# USB_power.net
KiCad netlist of a schematic drawn in Altium Designer
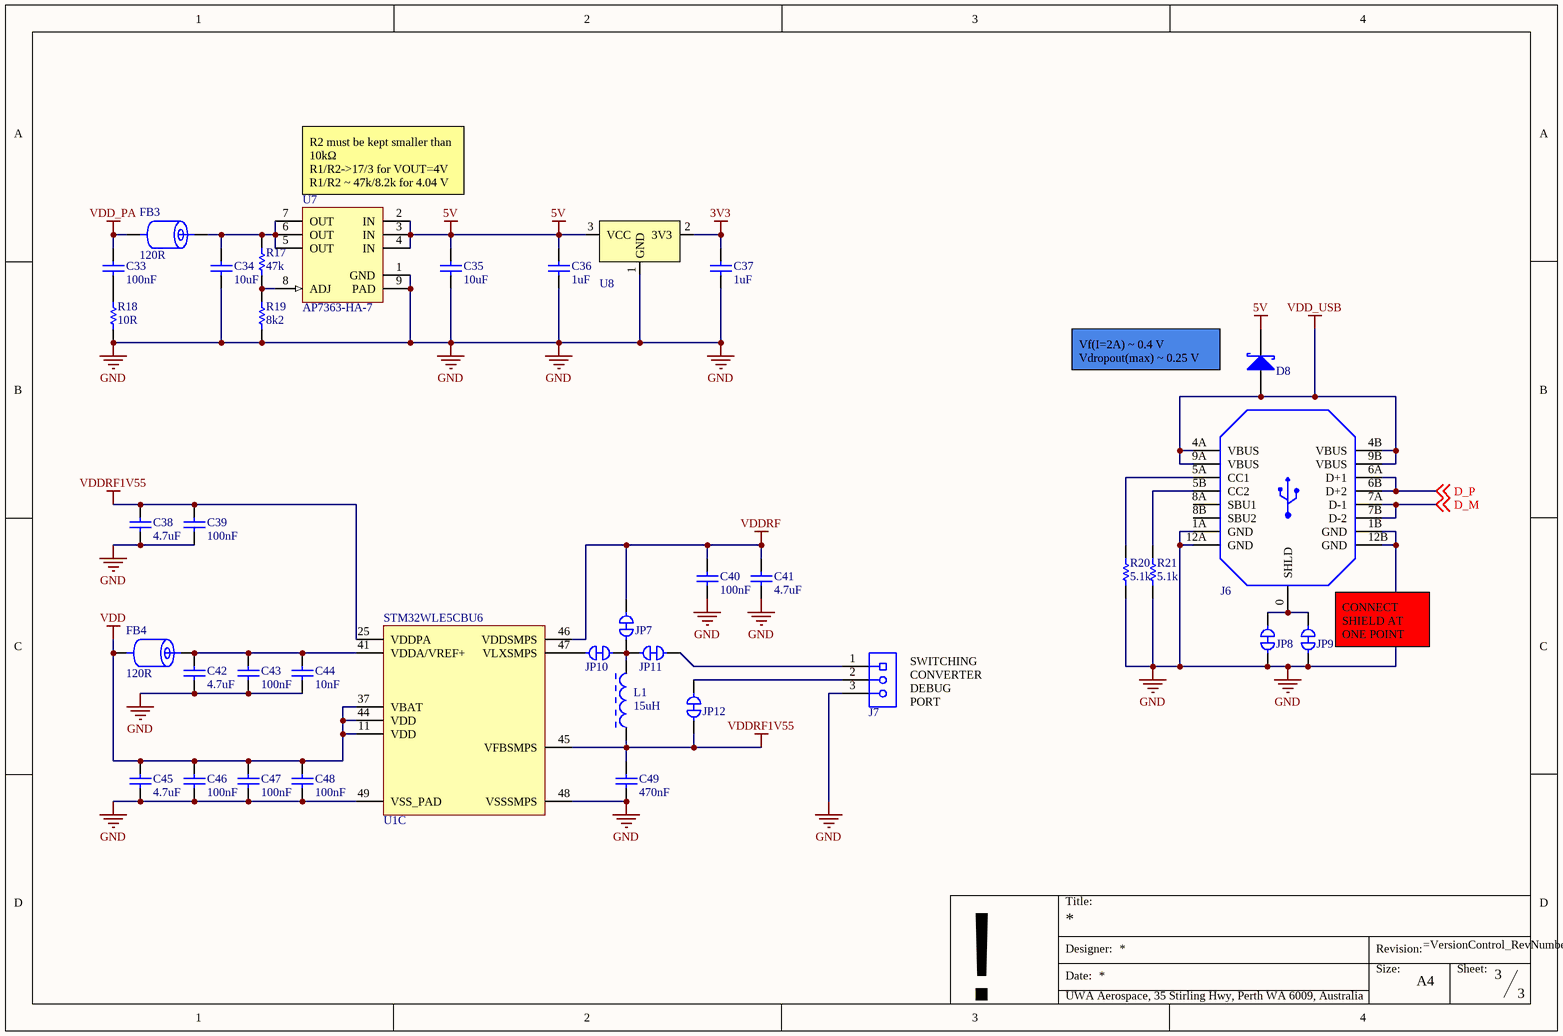
[diagram p0: USB & power.SchDoc]

(export (version "E")
  (design (tool "Eeschema 10.0.6"))
  (components
    (comp (ref "C33")
      (value "100nF")
      (footprint "CAPC1608X10N")
      (description "Cap Ceramic 0.1uF 50V X7R 20% SMD 0603 125C T/R")
      (fields (field (name "TOLERANCE") "20%") (field (name "Comment") "C0603C104M5RACTU"))
      (libsource (lib "UWA Aerospace") (part "C0603C104M5RACTU"))
    )
    (comp (ref "C34")
      (value "10uF")
      (footprint "CAPC2012X14N")
      (description "CAP CER 10UF 10V X5R 0805")
      (fields (field (name "VOLTAGE") "10V") (field (name "TOLERANCE") "10%"))
      (libsource (lib "UWA Aerospace") (part "C0603C104M5RACTU"))
    )
    (comp (ref "C35")
      (value "10uF")
      (footprint "CAPC2012X14N")
      (description "CAP CER 10UF 10V X5R 0805")
      (fields (field (name "VOLTAGE") "10V") (field (name "TOLERANCE") "10%"))
      (libsource (lib "UWA Aerospace") (part "C0603C104M5RACTU"))
    )
    (comp (ref "C36")
      (value "1uF")
      (footprint "CAPC1608X10N")
      (fields
        (field (name "VOLTAGE") "16V")
        (field (name "TOLERANCE") "10%")
        (field (name "Comment") "C0603C105K4RACTU")
      )
      (libsource (lib "UWA Aerospace") (part "C0603C104M5RACTU"))
    )
    (comp (ref "C37")
      (value "1uF")
      (footprint "CAPC1608X10N")
      (fields
        (field (name "VOLTAGE") "16V")
        (field (name "TOLERANCE") "10%")
        (field (name "Comment") "C0603C105K4RACTU")
      )
      (libsource (lib "UWA Aerospace") (part "C0603C104M5RACTU"))
    )
    (comp (ref "C38")
      (value "4.7uF")
      (footprint "CAPC1608X10N")
      (fields
        (field (name "TOLERANCE") "10%")
        (field (name "VOLTAGE") "6.3V")
        (field (name "Comment") "C0603C475K9PACTU")
      )
      (libsource (lib "UWA Aerospace") (part "C0603C104M5RACTU"))
    )
    (comp (ref "C39")
      (value "100nF")
      (footprint "CAPC1608X10N")
      (description "Cap Ceramic 0.1uF 50V X7R 20% SMD 0603 125C T/R")
      (fields (field (name "TOLERANCE") "20%") (field (name "Comment") "C0603C104M5RACTU"))
      (libsource (lib "UWA Aerospace") (part "C0603C104M5RACTU"))
    )
    (comp (ref "C40")
      (value "100nF")
      (footprint "CAPC1608X10N")
      (description "Cap Ceramic 0.1uF 50V X7R 20% SMD 0603 125C T/R")
      (fields (field (name "TOLERANCE") "20%") (field (name "Comment") "C0603C104M5RACTU"))
      (libsource (lib "UWA Aerospace") (part "C0603C104M5RACTU"))
    )
    (comp (ref "C41")
      (value "4.7uF")
      (footprint "CAPC1608X10N")
      (fields
        (field (name "TOLERANCE") "10%")
        (field (name "VOLTAGE") "6.3V")
        (field (name "Comment") "C0603C475K9PACTU")
      )
      (libsource (lib "UWA Aerospace") (part "C0603C104M5RACTU"))
    )
    (comp (ref "C42")
      (value "4.7uF")
      (footprint "CAPC1608X10N")
      (fields
        (field (name "TOLERANCE") "10%")
        (field (name "VOLTAGE") "6.3V")
        (field (name "Comment") "C0603C475K9PACTU")
      )
      (libsource (lib "UWA Aerospace") (part "C0603C104M5RACTU"))
    )
    (comp (ref "C43")
      (value "100nF")
      (footprint "CAPC1608X10N")
      (description "Cap Ceramic 0.1uF 50V X7R 20% SMD 0603 125C T/R")
      (fields (field (name "TOLERANCE") "20%") (field (name "Comment") "C0603C104M5RACTU"))
      (libsource (lib "UWA Aerospace") (part "C0603C104M5RACTU"))
    )
    (comp (ref "C44")
      (value "10nF")
      (footprint "CAPC1608X10N")
      (description "Cap Ceramic 0.01uF 50V X7R 5% SMD 0603 125C Paper T/R")
      (fields (field (name "TOLERANCE") "5%") (field (name "Comment") "C0603C103J5RACTU"))
      (libsource (lib "UWA Aerospace") (part "C0603C104M5RACTU"))
    )
    (comp (ref "C45")
      (value "4.7uF")
      (footprint "CAPC1608X10N")
      (fields
        (field (name "TOLERANCE") "10%")
        (field (name "VOLTAGE") "6.3V")
        (field (name "Comment") "C0603C475K9PACTU")
      )
      (libsource (lib "UWA Aerospace") (part "C0603C104M5RACTU"))
    )
    (comp (ref "C46")
      (value "100nF")
      (footprint "CAPC1608X10N")
      (description "Cap Ceramic 0.1uF 50V X7R 20% SMD 0603 125C T/R")
      (fields (field (name "TOLERANCE") "20%") (field (name "Comment") "C0603C104M5RACTU"))
      (libsource (lib "UWA Aerospace") (part "C0603C104M5RACTU"))
    )
    (comp (ref "C47")
      (value "100nF")
      (footprint "CAPC1608X10N")
      (description "Cap Ceramic 0.1uF 50V X7R 20% SMD 0603 125C T/R")
      (fields (field (name "TOLERANCE") "20%") (field (name "Comment") "C0603C104M5RACTU"))
      (libsource (lib "UWA Aerospace") (part "C0603C104M5RACTU"))
    )
    (comp (ref "C48")
      (value "100nF")
      (footprint "CAPC1608X10N")
      (description "Cap Ceramic 0.1uF 50V X7R 20% SMD 0603 125C T/R")
      (fields (field (name "TOLERANCE") "20%") (field (name "Comment") "C0603C104M5RACTU"))
      (libsource (lib "UWA Aerospace") (part "C0603C104M5RACTU"))
    )
    (comp (ref "C49")
      (value "470nF")
      (footprint "CAPC1608X10N")
      (description "CAP CER 0.47UF 25V X7R 0603")
      (fields (field (name "TOLERANCE") "10%") (field (name "Comment") "CL10B474KA8NNNC"))
      (libsource (lib "UWA Aerospace") (part "C0603C104M5RACTU"))
    )
    (comp (ref "D8")
      (value "SS54")
      (footprint "DIOM4226X20N")
      (libsource (lib "UWA Aerospace") (part "Diode - Schottky"))
    )
    (comp (ref "FB3")
      (value "120R")
      (footprint "INDC1608X10N")
      (description "Ferrite Beads Multi-Layer High Current 120Ohm 25% 100MHz 2A 0.05Ohm DCR 0603 T/R")
      (fields (field (name "Comment") "PE-0603PFB121ST"))
      (libsource (lib "UWA Aerospace") (part "Ferrite Bead"))
    )
    (comp (ref "FB4")
      (value "120R")
      (footprint "INDC1608X10N")
      (description "Ferrite Beads Multi-Layer High Current 120Ohm 25% 100MHz 2A 0.05Ohm DCR 0603 T/R")
      (fields (field (name "Comment") "PE-0603PFB121ST"))
      (libsource (lib "UWA Aerospace") (part "Ferrite Bead"))
    )
    (comp (ref "J6")
      (value "USB4105-GF-A")
      (footprint "GCT_USB4105-GF-A")
      (description "Conn USB 2.0 Type C RCP 24 POS 0.3mm/0.5mm Solder RA SMD 24 Terminal 1 Port T/R")
      (libsource (lib "UWA Aerospace") (part "Connector - USB Type-C (16 pins, USB 2.0)"))
    )
    (comp (ref "J7")
      (value "10129378-903001BLF")
      (footprint "10129378-903001BLF-Footprint-1")
      (description "Conn Unshrouded Header HDR 3 POS 2.54mm Solder ST Thru-Hole Poly Bag")
      (libsource (lib "UWA Aerospace") (part "10129378-903001BLF"))
    )
    (comp (ref "JP7")
      (value "RC0603FR-070RL")
      (footprint "RESC1608X05N")
      (description "RC Series 0603 0.1 W 0 Ohm Jumper Surface Mount Thick Film Chip Resistor")
      (fields (field (name "TOLERANCE") "1%"))
      (libsource (lib "UWA Aerospace") (part "Jumper - Closed"))
    )
    (comp (ref "JP8")
      (value "RC0603FR-070RL")
      (footprint "RESC1608X05N")
      (description "RC Series 0603 0.1 W 0 Ohm Jumper Surface Mount Thick Film Chip Resistor")
      (fields (field (name "TOLERANCE") "1%"))
      (libsource (lib "UWA Aerospace") (part "Jumper - Closed"))
    )
    (comp (ref "JP9")
      (value "RC0603FR-070RL")
      (footprint "RESC1608X05N")
      (description "RC Series 0603 0.1 W 0 Ohm Jumper Surface Mount Thick Film Chip Resistor")
      (fields (field (name "TOLERANCE") "1%"))
      (libsource (lib "UWA Aerospace") (part "Jumper - Closed"))
    )
    (comp (ref "JP10")
      (value "RC0603FR-070RL")
      (footprint "RESC1608X05N")
      (description "RC Series 0603 0.1 W 0 Ohm Jumper Surface Mount Thick Film Chip Resistor")
      (fields (field (name "TOLERANCE") "1%"))
      (libsource (lib "UWA Aerospace") (part "Jumper - Closed"))
    )
    (comp (ref "JP11")
      (value "RC0603FR-070RL")
      (footprint "RESC1608X05N")
      (description "RC Series 0603 0.1 W 0 Ohm Jumper Surface Mount Thick Film Chip Resistor")
      (fields (field (name "TOLERANCE") "1%"))
      (libsource (lib "UWA Aerospace") (part "Jumper - Closed"))
    )
    (comp (ref "JP12")
      (value "RC0603FR-070RL")
      (footprint "RESC1608X05N")
      (description "RC Series 0603 0.1 W 0 Ohm Jumper Surface Mount Thick Film Chip Resistor")
      (fields (field (name "TOLERANCE") "1%"))
      (libsource (lib "UWA Aerospace") (part "Jumper - Closed"))
    )
    (comp (ref "L1")
      (value "15uH")
      (footprint "INDC2012X14N")
      (description "Inductor Power Shielded Multi-Layer 15uH 20% 2MHz Ferrite 0.25A 1.235Ohm DCR 0805 T/R")
      (fields (field (name "TOLERANCE") "20%") (field (name "Comment") "MLZ2012M150WT000"))
      (libsource (lib "UWA Aerospace") (part "Inductor - Ferrite Core"))
    )
    (comp (ref "R17")
      (value "47k")
      (footprint "RESC1608X05N")
      (description "Res Thick Film 0603 47K Ohm 1% 1/10W ±100ppm/°C Molded SMD Punched Carrier T/R")
      (fields (field (name "TOLERANCE") "1%") (field (name "Comment") "ERJ3EKF4702V"))
      (libsource (lib "UWA Aerospace") (part "Resistor"))
    )
    (comp (ref "R18")
      (value "10R")
      (footprint "RESC1005X04N")
      (description "Res Thick Film 0402 10 Ohm 5% 1/5W ±200ppm/°C Molded SMD Punched Paper T/R")
      (fields (field (name "TOLERANCE") "5%") (field (name "Comment") "ERJ-PA2J100X"))
      (libsource (lib "UWA Aerospace") (part "Resistor"))
    )
    (comp (ref "R19")
      (value "8k2")
      (footprint "RESC1608X05N")
      (description "Res Thick Film 0603 8.2K Ohm 5% 1/10W ±200ppm/°C Molded SMD Paper T/R")
      (fields (field (name "TOLERANCE") "5%") (field (name "Comment") "CRCW06038K20JNEAC"))
      (libsource (lib "UWA Aerospace") (part "Resistor"))
    )
    (comp (ref "R20")
      (value "5.1k")
      (footprint "RESC1608X06N")
      (description "Res Thick Film 0603 5.1K Ohm 1% 1/10W ±100ppm/°C Molded SMD SMD Paper T/R")
      (fields (field (name "TOLERANCE") "1%") (field (name "Comment") "CRCW06035K10FKEA"))
      (libsource (lib "UWA Aerospace") (part "Resistor"))
    )
    (comp (ref "R21")
      (value "5.1k")
      (footprint "RESC1608X06N")
      (description "Res Thick Film 0603 5.1K Ohm 1% 1/10W ±100ppm/°C Molded SMD SMD Paper T/R")
      (fields (field (name "TOLERANCE") "1%") (field (name "Comment") "CRCW06035K10FKEA"))
      (libsource (lib "UWA Aerospace") (part "Resistor"))
    )
    (comp (ref "U1")
      (value "STM32WLE5CBU6")
      (footprint "QFN50P700X700X60_HS-49L")
      (description "Microcontroller 32-Bit Arm Cortex-M4 RISC 128Kbyte 1.8V to 3.6V 48-Pin UFQFPN Industrial")
      (libsource (lib "UWA Aerospace") (part "STM32WLE5CBU6-Symbol-1"))
    )
    (comp (ref "U7")
      (value "AP7363-HA-7")
      (footprint "SON50P300X63_HS-9M")
      (description "LDO Regulator Pos 0.6V to 5V 1.5A 8-Pin U-DFN2030 T/R")
      (libsource (lib "UWA Aerospace") (part "AP7363-HA-7-Symbol-1"))
    )
    (comp (ref "U8")
      (value "XC6206P332MR")
      (footprint "SOT95P280X120-3N")
      (description "IC REG LINEAR 3.3V 200MA SOT23")
      (libsource (lib "UWA Aerospace") (part "XC6206P332MR-Symbol-1"))
    )
  )
  (nets
    (net (code "1") (name "3V3") (class "Default")
      (node (ref "C37") (pin "2") (pinfunction "2_2") (pintype "passive"))
      (node (ref "U8") (pin "2") (pinfunction "3V3_2") (pintype "passive"))
    )
    (net (code "2") (name "5V") (class "Default")
      (node (ref "C35") (pin "2") (pinfunction "2_2") (pintype "passive"))
      (node (ref "C36") (pin "2") (pinfunction "2_2") (pintype "passive"))
      (node (ref "D8") (pin "2") (pinfunction "K_2") (pintype "passive"))
      (node (ref "U7") (pin "2") (pinfunction "IN_2") (pintype "power_in"))
      (node (ref "U7") (pin "3") (pinfunction "IN_3") (pintype "power_in"))
      (node (ref "U7") (pin "4") (pinfunction "IN_4") (pintype "power_in"))
      (node (ref "U8") (pin "3") (pinfunction "VCC_3") (pintype "passive"))
    )
    (net (code "3") (name "D_M") (class "Default")
      (node (ref "J6") (pin "7A") (pinfunction "D-1_7A") (pintype "passive"))
      (node (ref "J6") (pin "7B") (pinfunction "D-2_7B") (pintype "passive"))
    )
    (net (code "4") (name "D_P") (class "Default")
      (node (ref "J6") (pin "6A") (pinfunction "D+1_6A") (pintype "passive"))
      (node (ref "J6") (pin "6B") (pinfunction "D+2_6B") (pintype "passive"))
    )
    (net (code "5") (name "GND") (class "Default")
      (node (ref "C34") (pin "1") (pinfunction "1_1") (pintype "passive"))
      (node (ref "C35") (pin "1") (pinfunction "1_1") (pintype "passive"))
      (node (ref "C36") (pin "1") (pinfunction "1_1") (pintype "passive"))
      (node (ref "C37") (pin "1") (pinfunction "1_1") (pintype "passive"))
      (node (ref "C38") (pin "1") (pinfunction "1_1") (pintype "passive"))
      (node (ref "C39") (pin "1") (pinfunction "1_1") (pintype "passive"))
      (node (ref "C40") (pin "1") (pinfunction "1_1") (pintype "passive"))
      (node (ref "C41") (pin "1") (pinfunction "1_1") (pintype "passive"))
      (node (ref "C42") (pin "1") (pinfunction "1_1") (pintype "passive"))
      (node (ref "C43") (pin "1") (pinfunction "1_1") (pintype "passive"))
      (node (ref "C44") (pin "1") (pinfunction "1_1") (pintype "passive"))
      (node (ref "C45") (pin "1") (pinfunction "1_1") (pintype "passive"))
      (node (ref "C46") (pin "1") (pinfunction "1_1") (pintype "passive"))
      (node (ref "C47") (pin "1") (pinfunction "1_1") (pintype "passive"))
      (node (ref "C48") (pin "1") (pinfunction "1_1") (pintype "passive"))
      (node (ref "C49") (pin "1") (pinfunction "1_1") (pintype "passive"))
      (node (ref "J6") (pin "12A") (pinfunction "GND_12A") (pintype "passive"))
      (node (ref "J6") (pin "12B") (pinfunction "GND_12B") (pintype "passive"))
      (node (ref "J6") (pin "1A") (pinfunction "GND_1A") (pintype "passive"))
      (node (ref "J6") (pin "1B") (pinfunction "GND_1B") (pintype "passive"))
      (node (ref "J7") (pin "3") (pinfunction "3_3") (pintype "passive"))
      (node (ref "JP8") (pin "1") (pinfunction "1_1") (pintype "passive"))
      (node (ref "JP9") (pin "1") (pinfunction "1_1") (pintype "passive"))
      (node (ref "R18") (pin "1") (pinfunction "1_1") (pintype "passive"))
      (node (ref "R19") (pin "2") (pinfunction "2_2") (pintype "passive"))
      (node (ref "R20") (pin "1") (pinfunction "1_1") (pintype "passive"))
      (node (ref "R21") (pin "2") (pinfunction "2_2") (pintype "passive"))
      (node (ref "U1") (pin "48") (pinfunction "VSSSMPS_48") (pintype "power_in"))
      (node (ref "U1") (pin "49") (pinfunction "VSS_PAD_49") (pintype "power_in"))
      (node (ref "U7") (pin "1") (pinfunction "GND_1") (pintype "power_in"))
      (node (ref "U7") (pin "9") (pinfunction "PAD_9") (pintype "power_in"))
      (node (ref "U8") (pin "1") (pinfunction "GND_1") (pintype "passive"))
    )
    (net (code "6") (name "Net-(C33-Pad1)") (class "Default")
      (node (ref "C33") (pin "1") (pinfunction "1_1") (pintype "passive"))
      (node (ref "R18") (pin "2") (pinfunction "2_2") (pintype "passive"))
    )
    (net (code "7") (name "Net-(C34-Pad2)") (class "Default")
      (node (ref "C34") (pin "2") (pinfunction "2_2") (pintype "passive"))
      (node (ref "FB3") (pin "1") (pinfunction "1_1") (pintype "passive"))
      (node (ref "R17") (pin "2") (pinfunction "2_2") (pintype "passive"))
      (node (ref "U7") (pin "5") (pinfunction "OUT_5") (pintype "power_in"))
      (node (ref "U7") (pin "6") (pinfunction "OUT_6") (pintype "power_in"))
      (node (ref "U7") (pin "7") (pinfunction "OUT_7") (pintype "power_in"))
    )
    (net (code "8") (name "Net-(J6-CC1)") (class "Default")
      (node (ref "J6") (pin "5A") (pinfunction "CC1_5A") (pintype "passive"))
      (node (ref "R20") (pin "2") (pinfunction "2_2") (pintype "passive"))
    )
    (net (code "9") (name "Net-(J6-CC2)") (class "Default")
      (node (ref "J6") (pin "5B") (pinfunction "CC2_5B") (pintype "passive"))
      (node (ref "R21") (pin "1") (pinfunction "1_1") (pintype "passive"))
    )
    (net (code "10") (name "Net-(J6-SHLD)") (class "Default")
      (node (ref "J6") (pin "0") (pinfunction "SHLD_0") (pintype "passive"))
      (node (ref "JP8") (pin "2") (pinfunction "2_2") (pintype "passive"))
      (node (ref "JP9") (pin "2") (pinfunction "2_2") (pintype "passive"))
    )
    (net (code "11") (name "Net-(J7-Pad1)") (class "Default")
      (node (ref "J7") (pin "1") (pinfunction "1_1") (pintype "passive"))
      (node (ref "JP11") (pin "1") (pinfunction "1_1") (pintype "passive"))
    )
    (net (code "12") (name "Net-(J7-Pad2)") (class "Default")
      (node (ref "J7") (pin "2") (pinfunction "2_2") (pintype "passive"))
      (node (ref "JP12") (pin "1") (pinfunction "1_1") (pintype "passive"))
    )
    (net (code "13") (name "Net-(JP10-Pad2)") (class "Default")
      (node (ref "JP10") (pin "2") (pinfunction "2_2") (pintype "passive"))
      (node (ref "JP11") (pin "2") (pinfunction "2_2") (pintype "passive"))
      (node (ref "JP7") (pin "1") (pinfunction "1_1") (pintype "passive"))
      (node (ref "L1") (pin "2") (pinfunction "2_2") (pintype "passive"))
    )
    (net (code "14") (name "Net-(U1C-VDDA{slash}VREF+)") (class "Default")
      (node (ref "C42") (pin "2") (pinfunction "2_2") (pintype "passive"))
      (node (ref "C43") (pin "2") (pinfunction "2_2") (pintype "passive"))
      (node (ref "C44") (pin "2") (pinfunction "2_2") (pintype "passive"))
      (node (ref "FB4") (pin "1") (pinfunction "1_1") (pintype "passive"))
      (node (ref "U1") (pin "41") (pinfunction "VDDA/VREF+_41") (pintype "power_in"))
    )
    (net (code "15") (name "Net-(U1C-VLXSMPS)") (class "Default")
      (node (ref "JP10") (pin "1") (pinfunction "1_1") (pintype "passive"))
      (node (ref "U1") (pin "47") (pinfunction "VLXSMPS_47") (pintype "power_in"))
    )
    (net (code "16") (name "Net-(U7-ADJ)") (class "Default")
      (node (ref "R17") (pin "1") (pinfunction "1_1") (pintype "passive"))
      (node (ref "R19") (pin "1") (pinfunction "1_1") (pintype "passive"))
      (node (ref "U7") (pin "8") (pinfunction "ADJ_8") (pintype "input"))
    )
    (net (code "17") (name "VDD") (class "Default")
      (node (ref "C45") (pin "2") (pinfunction "2_2") (pintype "passive"))
      (node (ref "C46") (pin "2") (pinfunction "2_2") (pintype "passive"))
      (node (ref "C47") (pin "2") (pinfunction "2_2") (pintype "passive"))
      (node (ref "C48") (pin "2") (pinfunction "2_2") (pintype "passive"))
      (node (ref "FB4") (pin "2") (pinfunction "2_2") (pintype "passive"))
      (node (ref "U1") (pin "11") (pinfunction "VDD_11") (pintype "power_in"))
      (node (ref "U1") (pin "37") (pinfunction "VBAT_37") (pintype "power_in"))
      (node (ref "U1") (pin "44") (pinfunction "VDD_44") (pintype "power_in"))
    )
    (net (code "18") (name "VDDRF") (class "Default")
      (node (ref "C40") (pin "2") (pinfunction "2_2") (pintype "passive"))
      (node (ref "C41") (pin "2") (pinfunction "2_2") (pintype "passive"))
      (node (ref "JP7") (pin "2") (pinfunction "2_2") (pintype "passive"))
      (node (ref "U1") (pin "46") (pinfunction "VDDSMPS_46") (pintype "power_in"))
    )
    (net (code "19") (name "VDDRF1V55") (class "Default")
      (node (ref "C38") (pin "2") (pinfunction "2_2") (pintype "passive"))
      (node (ref "C39") (pin "2") (pinfunction "2_2") (pintype "passive"))
      (node (ref "C49") (pin "2") (pinfunction "2_2") (pintype "passive"))
      (node (ref "JP12") (pin "2") (pinfunction "2_2") (pintype "passive"))
      (node (ref "L1") (pin "1") (pinfunction "1_1") (pintype "passive"))
      (node (ref "U1") (pin "25") (pinfunction "VDDPA_25") (pintype "power_in"))
      (node (ref "U1") (pin "45") (pinfunction "VFBSMPS_45") (pintype "power_in"))
    )
    (net (code "20") (name "VDD_PA") (class "Default")
      (node (ref "C33") (pin "2") (pinfunction "2_2") (pintype "passive"))
      (node (ref "FB3") (pin "2") (pinfunction "2_2") (pintype "passive"))
    )
    (net (code "21") (name "VDD_USB") (class "Default")
      (node (ref "D8") (pin "1") (pinfunction "A_1") (pintype "passive"))
      (node (ref "J6") (pin "4A") (pinfunction "VBUS_4A") (pintype "passive"))
      (node (ref "J6") (pin "4B") (pinfunction "VBUS_4B") (pintype "passive"))
      (node (ref "J6") (pin "9A") (pinfunction "VBUS_9A") (pintype "passive"))
      (node (ref "J6") (pin "9B") (pinfunction "VBUS_9B") (pintype "passive"))
    )
    (net (code "22") (name "unconnected-(J6-SBU1-Pad8A)") (class "Default")
      (node (ref "J6") (pin "8A") (pinfunction "SBU1_8A") (pintype "passive"))
    )
    (net (code "23") (name "unconnected-(J6-SBU2-Pad8B)") (class "Default")
      (node (ref "J6") (pin "8B") (pinfunction "SBU2_8B") (pintype "passive"))
    )
  )
)
